# Model5.net
KiCad netlist of a schematic drawn in EAGLE
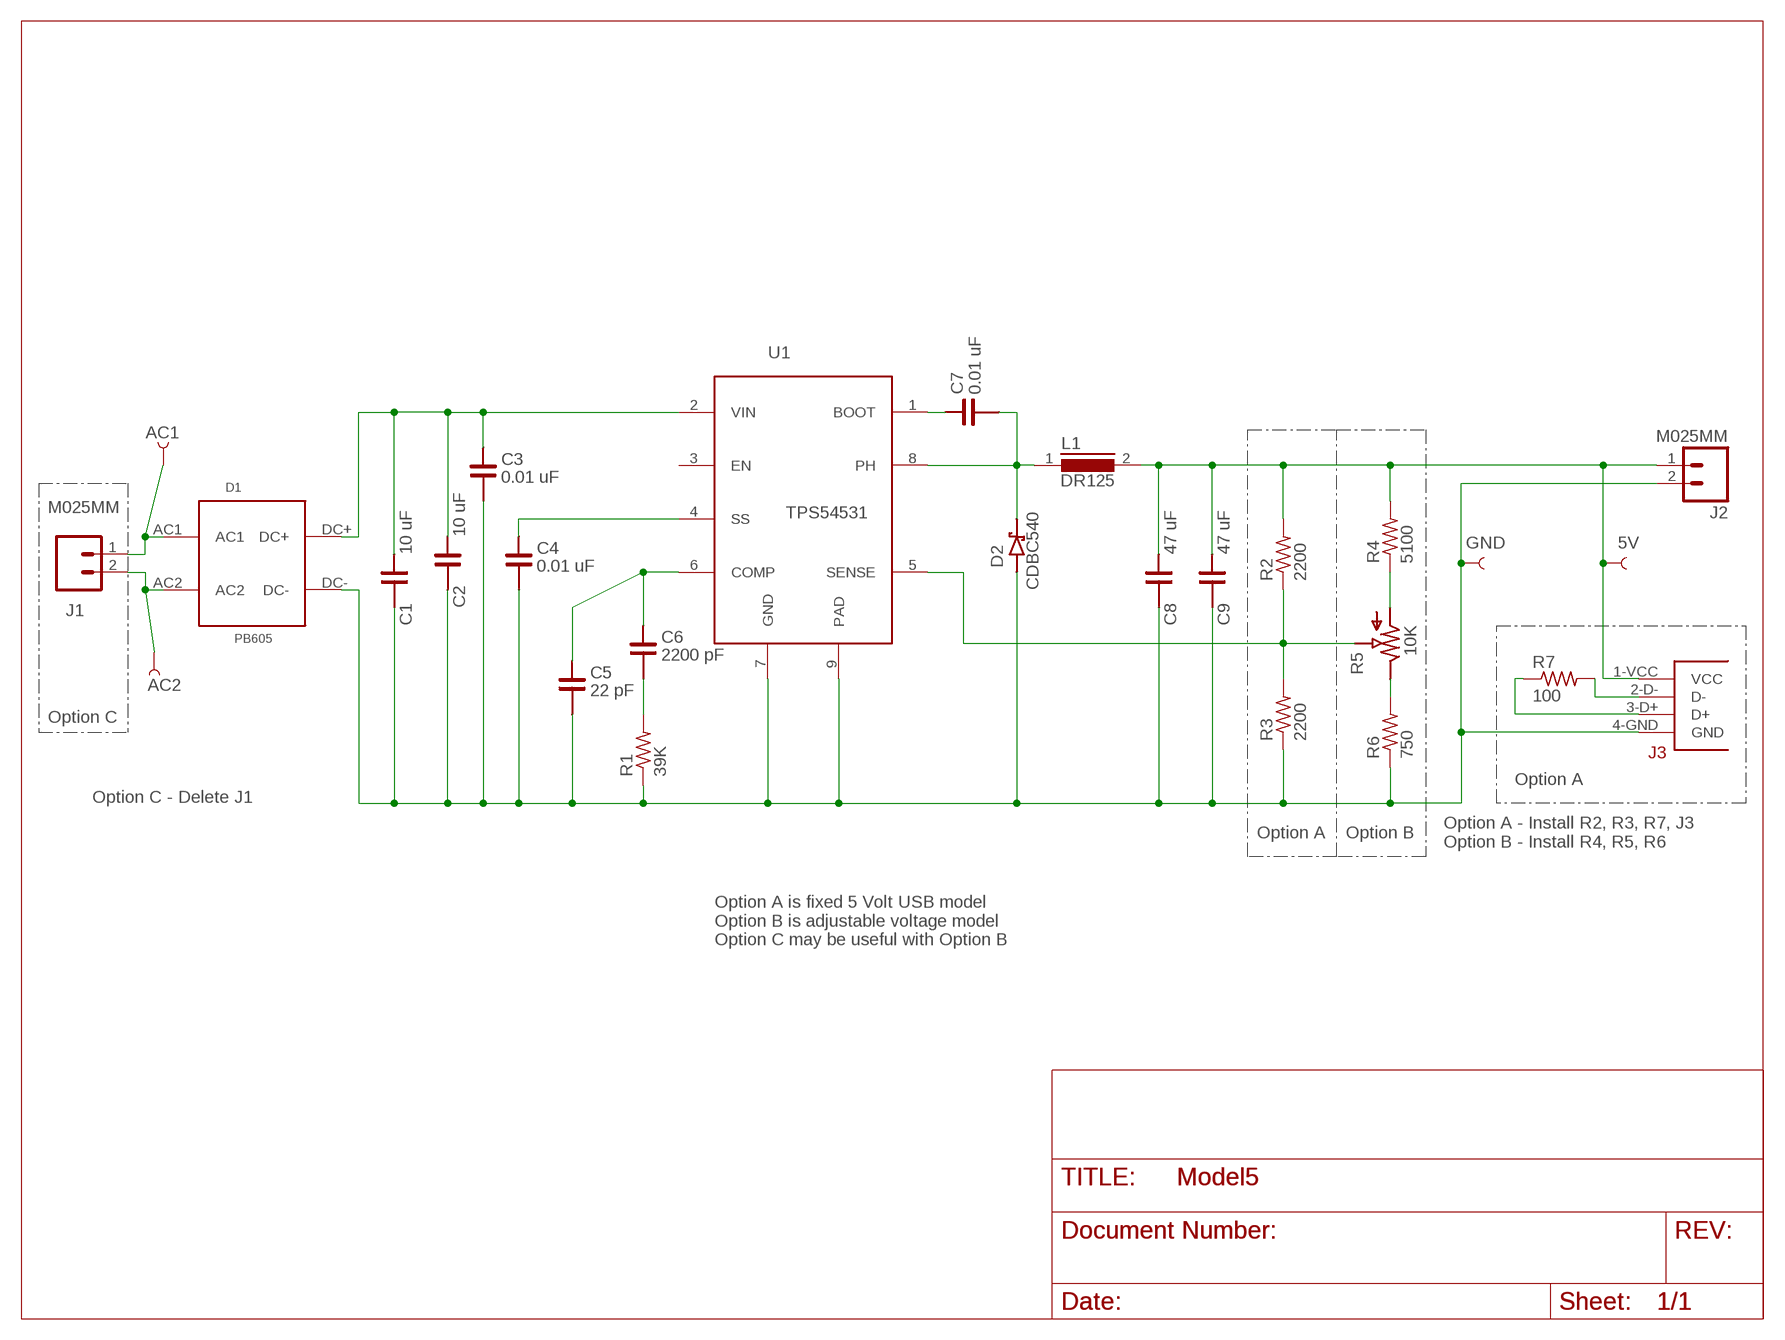
[diagram p0: schematic, sheet 1]

(export (version "E")
  (design (tool "Eeschema 10.0.6"))
  (components
    (comp (ref "5V")
      (value "TEST-POINT3")
      (footprint "eagle-import:PAD.03X.03")
      (libsource (lib "eagle-import") (part "TEST-POINT3"))
    )
    (comp (ref "AC1")
      (value "TEST-POINT3")
      (footprint "eagle-import:PAD.03X.03")
      (libsource (lib "eagle-import") (part "TEST-POINT3"))
    )
    (comp (ref "AC2")
      (value "TEST-POINT3")
      (footprint "eagle-import:PAD.03X.03")
      (libsource (lib "eagle-import") (part "TEST-POINT3"))
    )
    (comp (ref "C1")
      (value "10 uF")
      (footprint "eagle-import:1210")
      (libsource (lib "eagle-import") (part "CN-1210"))
    )
    (comp (ref "C2")
      (value "10 uF")
      (footprint "eagle-import:1210")
      (libsource (lib "eagle-import") (part "CN-1210"))
    )
    (comp (ref "C3")
      (value "0.01 uF")
      (footprint "eagle-import:0805")
      (libsource (lib "eagle-import") (part "CN-0805"))
    )
    (comp (ref "C4")
      (value "0.01 uF")
      (footprint "eagle-import:0805")
      (libsource (lib "eagle-import") (part "CN-0805"))
    )
    (comp (ref "C5")
      (value "22 pF")
      (footprint "eagle-import:0805")
      (libsource (lib "eagle-import") (part "CN-0805"))
    )
    (comp (ref "C6")
      (value "2200 pF")
      (footprint "eagle-import:0805")
      (libsource (lib "eagle-import") (part "CN-0805"))
    )
    (comp (ref "C7")
      (value "0.01 uF")
      (footprint "eagle-import:0805")
      (libsource (lib "eagle-import") (part "CN-0805"))
    )
    (comp (ref "C8")
      (value "47 uF")
      (footprint "eagle-import:C1206")
      (libsource (lib "eagle-import") (part "CN-1206"))
    )
    (comp (ref "C9")
      (value "47 uF")
      (footprint "eagle-import:C1206")
      (libsource (lib "eagle-import") (part "CN-1206"))
    )
    (comp (ref "D1")
      (value "PB605")
      (footprint "eagle-import:QUAD4PIN")
      (libsource (lib "eagle-import") (part "PB605"))
    )
    (comp (ref "D2")
      (value "CDBC540")
      (footprint "eagle-import:DO214AB")
      (libsource (lib "eagle-import") (part "CDBC540"))
    )
    (comp (ref "GND")
      (value "TEST-POINT3")
      (footprint "eagle-import:PAD.03X.03")
      (libsource (lib "eagle-import") (part "TEST-POINT3"))
    )
    (comp (ref "J1")
      (value "M025MM")
      (footprint "eagle-import:SCREWTERMINAL-5MM-2")
      (libsource (lib "eagle-import") (part "M025MM"))
    )
    (comp (ref "J2")
      (value "M025MM")
      (footprint "eagle-import:SCREWTERMINAL-5MM-2")
      (libsource (lib "eagle-import") (part "M025MM"))
    )
    (comp (ref "JP3")
      (value "87520-USB-A-FEMALE")
      (footprint "eagle-import:87520-USB-A-FEMALE")
      (libsource (lib "eagle-import") (part "87520-USB-A-FEMALE"))
    )
    (comp (ref "L1")
      (value "DR125")
      (footprint "eagle-import:DR125")
      (libsource (lib "eagle-import") (part "DR125"))
    )
    (comp (ref "R1")
      (value "39K")
      (footprint "eagle-import:R0805")
      (libsource (lib "eagle-import") (part "R-US_R0805"))
    )
    (comp (ref "R2")
      (value "2200")
      (footprint "eagle-import:R0805")
      (libsource (lib "eagle-import") (part "R-US_R0805"))
    )
    (comp (ref "R3")
      (value "2200")
      (footprint "eagle-import:R0805")
      (libsource (lib "eagle-import") (part "R-US_R0805"))
    )
    (comp (ref "R4")
      (value "5100")
      (footprint "eagle-import:R0805")
      (libsource (lib "eagle-import") (part "R-US_R0805"))
    )
    (comp (ref "R5")
      (value "3214J")
      (footprint "eagle-import:3214J")
      (libsource (lib "eagle-import") (part "3214J"))
    )
    (comp (ref "R6")
      (value "750")
      (footprint "eagle-import:R0805")
      (libsource (lib "eagle-import") (part "R-US_R0805"))
    )
    (comp (ref "R7")
      (value "100")
      (footprint "eagle-import:R0805")
      (libsource (lib "eagle-import") (part "R-US_R0805"))
    )
    (comp (ref "U1")
      (value "TPS54531")
      (footprint "eagle-import:SOIC127P600X170-9N")
      (libsource (lib "eagle-import") (part "TPS54531"))
    )
  )
  (nets
    (net (code "1") (name "Net-(5V-1)") (class "Default")
      (node (ref "5V") (pin "P$1") (pinfunction "1_P$1") (pintype "bidirectional"))
      (node (ref "C8") (pin "1") (pinfunction "P$1_1") (pintype "bidirectional"))
      (node (ref "C9") (pin "1") (pinfunction "P$1_1") (pintype "bidirectional"))
      (node (ref "J2") (pin "1") (pinfunction "1_1") (pintype "passive"))
      (node (ref "JP3") (pin "1-VCC") (pinfunction "VCC_1-VCC") (pintype "power_in"))
      (node (ref "L1") (pin "2") (pinfunction "2_2") (pintype "passive"))
      (node (ref "R2") (pin "2") (pinfunction "2_2") (pintype "passive"))
      (node (ref "R4") (pin "2") (pinfunction "2_2") (pintype "passive"))
    )
    (net (code "2") (name "Net-(AC1-1)") (class "Default")
      (node (ref "AC1") (pin "P$1") (pinfunction "1_P$1") (pintype "bidirectional"))
      (node (ref "D1") (pin "AC1") (pinfunction "AC1_AC1") (pintype "power_in"))
      (node (ref "J1") (pin "1") (pinfunction "1_1") (pintype "passive"))
    )
    (net (code "3") (name "Net-(AC2-1)") (class "Default")
      (node (ref "AC2") (pin "P$1") (pinfunction "1_P$1") (pintype "bidirectional"))
      (node (ref "D1") (pin "AC2") (pinfunction "AC2_AC2") (pintype "power_in"))
      (node (ref "J1") (pin "2") (pinfunction "2_2") (pintype "passive"))
    )
    (net (code "4") (name "Net-(C1-P$1)") (class "Default")
      (node (ref "C1") (pin "1") (pinfunction "P$1_1") (pintype "bidirectional"))
      (node (ref "C2") (pin "1") (pinfunction "P$1_1") (pintype "bidirectional"))
      (node (ref "C3") (pin "1") (pinfunction "P$1_1") (pintype "bidirectional"))
      (node (ref "D1") (pin "DC+") (pinfunction "DC+_DC+") (pintype "power_in"))
      (node (ref "U1") (pin "2") (pinfunction "VIN_2") (pintype "power_in"))
    )
    (net (code "5") (name "Net-(C1-P$2)") (class "Default")
      (node (ref "C1") (pin "2") (pinfunction "P$2_2") (pintype "bidirectional"))
      (node (ref "C2") (pin "2") (pinfunction "P$2_2") (pintype "bidirectional"))
      (node (ref "C3") (pin "2") (pinfunction "P$2_2") (pintype "bidirectional"))
      (node (ref "C4") (pin "2") (pinfunction "P$2_2") (pintype "bidirectional"))
      (node (ref "C5") (pin "2") (pinfunction "P$2_2") (pintype "bidirectional"))
      (node (ref "C8") (pin "2") (pinfunction "P$2_2") (pintype "bidirectional"))
      (node (ref "C9") (pin "2") (pinfunction "P$2_2") (pintype "bidirectional"))
      (node (ref "D1") (pin "DC-") (pinfunction "DC-_DC-") (pintype "power_in"))
      (node (ref "D2") (pin "ANODE") (pinfunction "P$1_ANODE") (pintype "input"))
      (node (ref "GND") (pin "P$1") (pinfunction "1_P$1") (pintype "bidirectional"))
      (node (ref "J2") (pin "2") (pinfunction "2_2") (pintype "passive"))
      (node (ref "JP3") (pin "4-GND") (pinfunction "GND_4-GND") (pintype "power_in"))
      (node (ref "R1") (pin "1") (pinfunction "1_1") (pintype "passive"))
      (node (ref "R3") (pin "1") (pinfunction "1_1") (pintype "passive"))
      (node (ref "R6") (pin "1") (pinfunction "1_1") (pintype "passive"))
      (node (ref "U1") (pin "7") (pinfunction "GND_7") (pintype "power_in"))
      (node (ref "U1") (pin "9") (pinfunction "PAD_9") (pintype "power_in"))
    )
    (net (code "6") (name "Net-(C4-P$1)") (class "Default")
      (node (ref "C4") (pin "1") (pinfunction "P$1_1") (pintype "bidirectional"))
      (node (ref "U1") (pin "4") (pinfunction "SS_4") (pintype "bidirectional"))
    )
    (net (code "7") (name "Net-(C5-P$1)") (class "Default")
      (node (ref "C5") (pin "1") (pinfunction "P$1_1") (pintype "bidirectional"))
      (node (ref "C6") (pin "1") (pinfunction "P$1_1") (pintype "bidirectional"))
      (node (ref "U1") (pin "6") (pinfunction "COMP_6") (pintype "bidirectional"))
    )
    (net (code "8") (name "Net-(C6-P$2)") (class "Default")
      (node (ref "C6") (pin "2") (pinfunction "P$2_2") (pintype "bidirectional"))
      (node (ref "R1") (pin "2") (pinfunction "2_2") (pintype "passive"))
    )
    (net (code "9") (name "Net-(C7-P$1)") (class "Default")
      (node (ref "C7") (pin "1") (pinfunction "P$1_1") (pintype "bidirectional"))
      (node (ref "U1") (pin "1") (pinfunction "BOOT_1") (pintype "input"))
    )
    (net (code "10") (name "Net-(C7-P$2)") (class "Default")
      (node (ref "C7") (pin "2") (pinfunction "P$2_2") (pintype "bidirectional"))
      (node (ref "D2") (pin "CATHODE") (pinfunction "P$2_CATHODE") (pintype "output"))
      (node (ref "L1") (pin "1") (pinfunction "1_1") (pintype "passive"))
      (node (ref "U1") (pin "8") (pinfunction "PH_8") (pintype "power_in"))
    )
    (net (code "11") (name "Net-(JP3-D+)") (class "Default")
      (node (ref "JP3") (pin "3-D+") (pinfunction "D+_3-D+") (pintype "bidirectional"))
      (node (ref "R7") (pin "1") (pinfunction "1_1") (pintype "passive"))
    )
    (net (code "12") (name "Net-(JP3-D-)") (class "Default")
      (node (ref "JP3") (pin "2-D-") (pinfunction "D-_2-D-") (pintype "bidirectional"))
      (node (ref "R7") (pin "2") (pinfunction "2_2") (pintype "passive"))
    )
    (net (code "13") (name "Net-(R5-1)") (class "Default")
      (node (ref "R4") (pin "1") (pinfunction "1_1") (pintype "passive"))
      (node (ref "R5") (pin "P$1") (pinfunction "1_P$1") (pintype "bidirectional"))
    )
    (net (code "14") (name "Net-(R5-2)") (class "Default")
      (node (ref "R2") (pin "1") (pinfunction "1_1") (pintype "passive"))
      (node (ref "R3") (pin "2") (pinfunction "2_2") (pintype "passive"))
      (node (ref "R5") (pin "P$2") (pinfunction "2_P$2") (pintype "bidirectional"))
      (node (ref "U1") (pin "5") (pinfunction "SENSE_5") (pintype "bidirectional"))
    )
    (net (code "15") (name "Net-(R5-3)") (class "Default")
      (node (ref "R5") (pin "P$3") (pinfunction "3_P$3") (pintype "bidirectional"))
      (node (ref "R6") (pin "2") (pinfunction "2_2") (pintype "passive"))
    )
    (net (code "16") (name "unconnected-(U1-EN-Pad3)") (class "Default")
      (node (ref "U1") (pin "3") (pinfunction "EN_3") (pintype "input"))
    )
  )
)
